# 2021-03-01_HALO_Main_Board.net
KiCad netlist of a schematic drawn in EAGLE
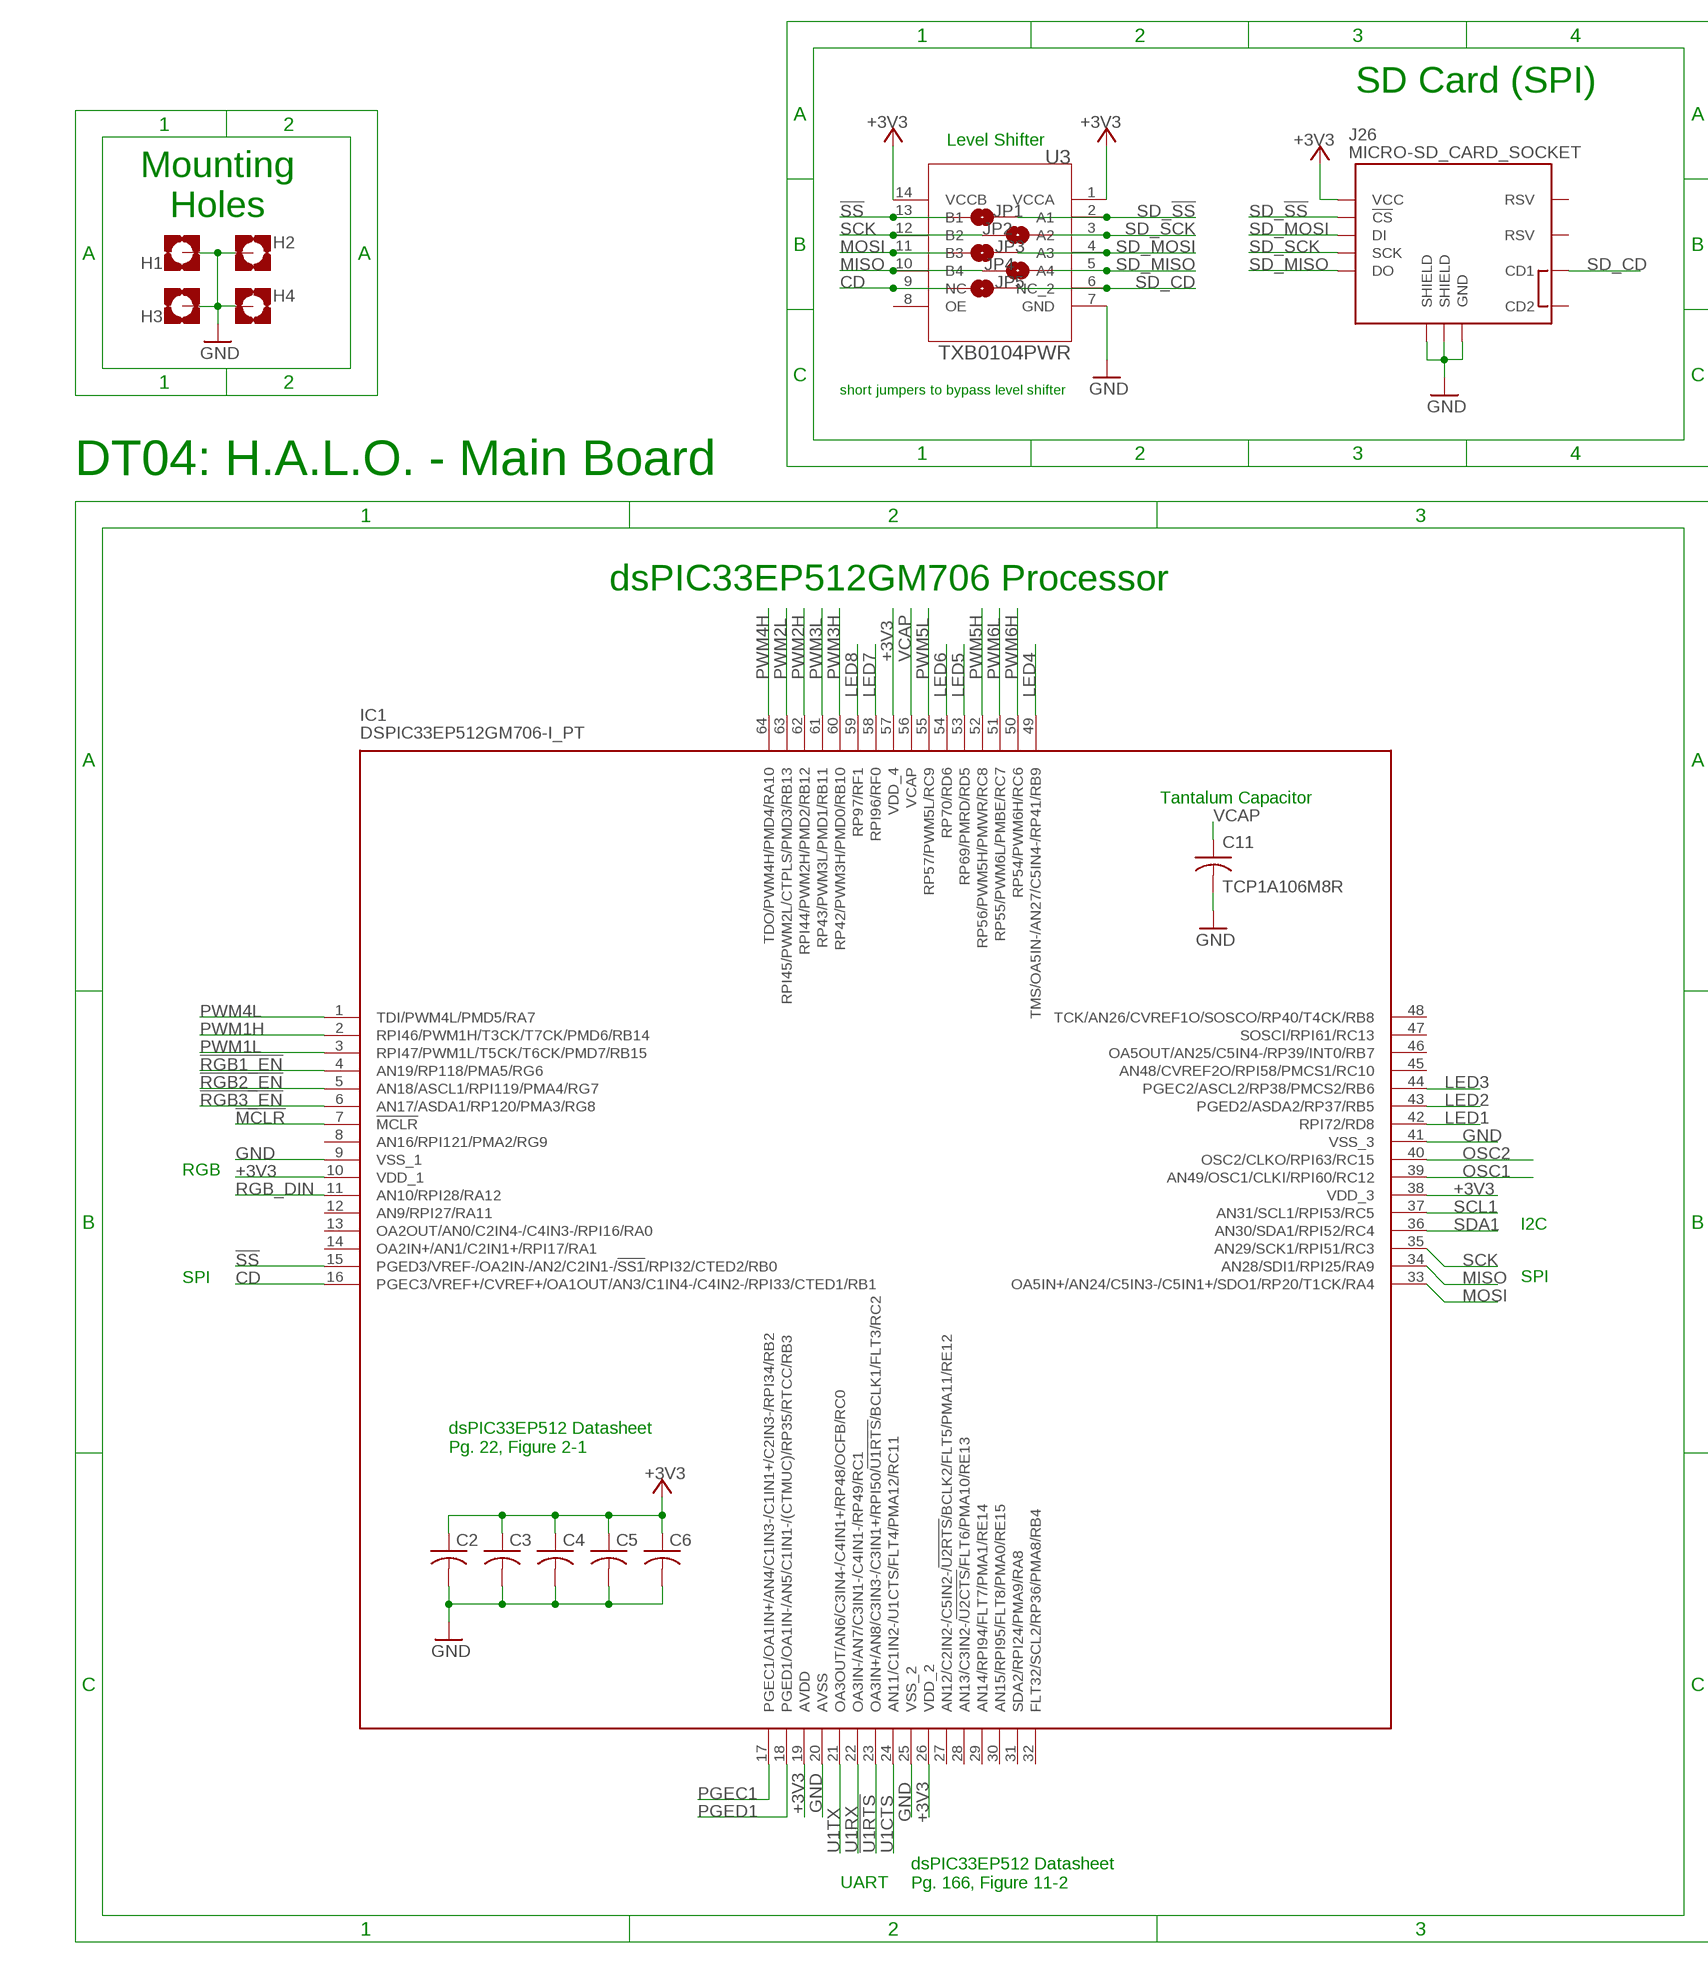
[diagram p0: schematic, sheet 1, part 1 of 2]
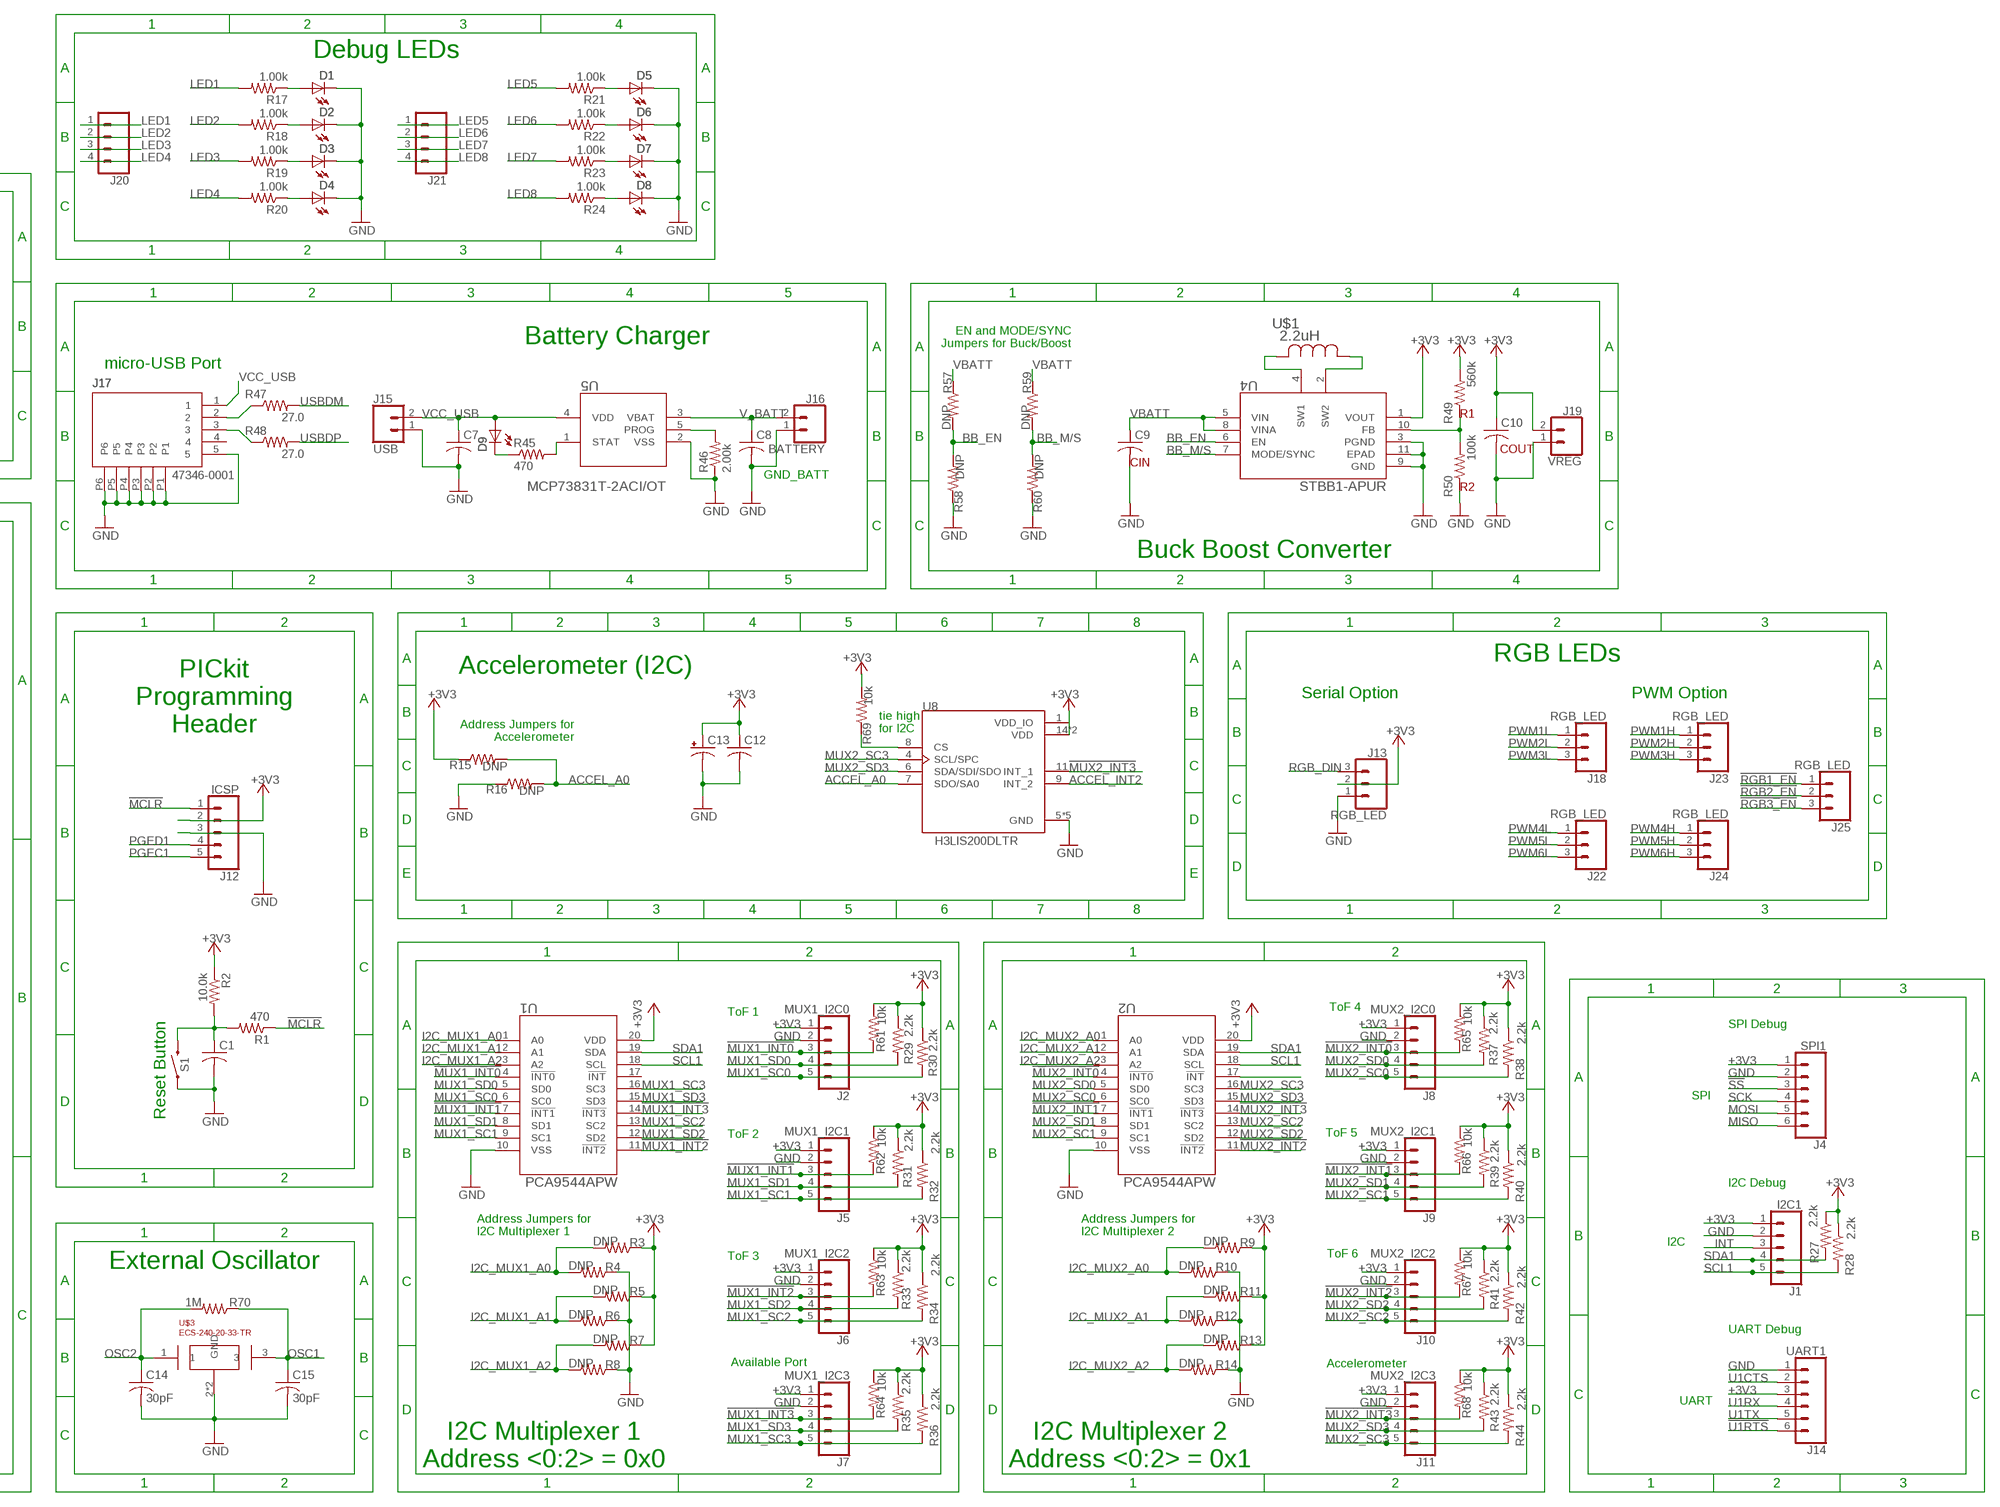
[diagram p1: schematic, sheet 1, part 2 of 2]

(export (version "E")
  (design (tool "Eeschema 10.0.6"))
  (components
    (comp (ref "C1")
      (value "0.1uF")
      (footprint "eagle-import:C0805")
      (libsource (lib "eagle-import") (part "rcl_C-USC0805"))
    )
    (comp (ref "C2")
      (value "0.1uF")
      (footprint "eagle-import:C0805")
      (libsource (lib "eagle-import") (part "rcl_C-USC0805"))
    )
    (comp (ref "C3")
      (value "0.1uF")
      (footprint "eagle-import:C0805")
      (libsource (lib "eagle-import") (part "rcl_C-USC0805"))
    )
    (comp (ref "C4")
      (value "0.1uF")
      (footprint "eagle-import:C0805")
      (libsource (lib "eagle-import") (part "rcl_C-USC0805"))
    )
    (comp (ref "C5")
      (value "0.1uF")
      (footprint "eagle-import:C0805")
      (libsource (lib "eagle-import") (part "rcl_C-USC0805"))
    )
    (comp (ref "C6")
      (value "0.1uF")
      (footprint "eagle-import:C0805")
      (libsource (lib "eagle-import") (part "rcl_C-USC0805"))
    )
    (comp (ref "C7")
      (value "4.7uF")
      (footprint "eagle-import:C0805")
      (libsource (lib "eagle-import") (part "rcl_C-USC0805"))
    )
    (comp (ref "C8")
      (value "4.7uF")
      (footprint "eagle-import:C0805")
      (libsource (lib "eagle-import") (part "rcl_C-USC0805"))
    )
    (comp (ref "C9")
      (value "10uF")
      (footprint "eagle-import:C0805")
      (libsource (lib "eagle-import") (part "rcl_C-USC0805"))
    )
    (comp (ref "C10")
      (value "22uF")
      (footprint "eagle-import:C0805")
      (libsource (lib "eagle-import") (part "rcl_C-USC0805"))
    )
    (comp (ref "C11")
      (value "TCP1A106M8R")
      (footprint "eagle-import:TCP_ROM")
      (libsource (lib "eagle-import") (part "TCP1A106M8R"))
    )
    (comp (ref "C12")
      (value "0.1uF")
      (footprint "eagle-import:C0805")
      (libsource (lib "eagle-import") (part "rcl_C-USC0805"))
    )
    (comp (ref "C13")
      (value "10uF")
      (footprint "eagle-import:EIA3216")
      (libsource (lib "eagle-import") (part "10UF-POLAR-EIA3216-16V-10%(TANT)"))
    )
    (comp (ref "C14")
      (value "30pF")
      (footprint "eagle-import:C0805")
      (libsource (lib "eagle-import") (part "C-USC0805"))
    )
    (comp (ref "C15")
      (value "30pF")
      (footprint "eagle-import:C0805")
      (libsource (lib "eagle-import") (part "C-USC0805"))
    )
    (comp (ref "D1")
      (value "CHIP-LED0805")
      (footprint "eagle-import:CHIP-LED0805")
      (libsource (lib "eagle-import") (part "CHIP-LED0805"))
    )
    (comp (ref "D2")
      (value "CHIP-LED0805")
      (footprint "eagle-import:CHIP-LED0805")
      (libsource (lib "eagle-import") (part "CHIP-LED0805"))
    )
    (comp (ref "D3")
      (value "CHIP-LED0805")
      (footprint "eagle-import:CHIP-LED0805")
      (libsource (lib "eagle-import") (part "CHIP-LED0805"))
    )
    (comp (ref "D4")
      (value "CHIP-LED0805")
      (footprint "eagle-import:CHIP-LED0805")
      (libsource (lib "eagle-import") (part "CHIP-LED0805"))
    )
    (comp (ref "D5")
      (value "CHIP-LED0805")
      (footprint "eagle-import:CHIP-LED0805")
      (libsource (lib "eagle-import") (part "CHIP-LED0805"))
    )
    (comp (ref "D6")
      (value "CHIP-LED0805")
      (footprint "eagle-import:CHIP-LED0805")
      (libsource (lib "eagle-import") (part "CHIP-LED0805"))
    )
    (comp (ref "D7")
      (value "CHIP-LED0805")
      (footprint "eagle-import:CHIP-LED0805")
      (libsource (lib "eagle-import") (part "CHIP-LED0805"))
    )
    (comp (ref "D8")
      (value "CHIP-LED0805")
      (footprint "eagle-import:CHIP-LED0805")
      (libsource (lib "eagle-import") (part "CHIP-LED0805"))
    )
    (comp (ref "D9")
      (value "CHIP-LED0805")
      (footprint "eagle-import:CHIP-LED0805")
      (libsource (lib "eagle-import") (part "CHIP-LED0805"))
    )
    (comp (ref "H1")
      (value "MOUNT-PAD-SQUARE3.0")
      (footprint "eagle-import:3,0-PAD-SQUARE")
      (libsource (lib "eagle-import") (part "MOUNT-PAD-SQUARE3.0"))
    )
    (comp (ref "H2")
      (value "MOUNT-PAD-SQUARE3.0")
      (footprint "eagle-import:3,0-PAD-SQUARE")
      (libsource (lib "eagle-import") (part "MOUNT-PAD-SQUARE3.0"))
    )
    (comp (ref "H3")
      (value "MOUNT-PAD-SQUARE3.0")
      (footprint "eagle-import:3,0-PAD-SQUARE")
      (libsource (lib "eagle-import") (part "MOUNT-PAD-SQUARE3.0"))
    )
    (comp (ref "H4")
      (value "MOUNT-PAD-SQUARE3.0")
      (footprint "eagle-import:3,0-PAD-SQUARE")
      (libsource (lib "eagle-import") (part "MOUNT-PAD-SQUARE3.0"))
    )
    (comp (ref "IC1")
      (value "DSPIC33EP512GM706-I_PT")
      (footprint "eagle-import:QFP50P1200X1200X120-64N")
      (fields
        (field (name "ARROW_PART_NUMBER") "DSPIC33EP512GM706-I/PT")
        (field (name "MOUSER_PART_NUMBER") "579-512GM706-I/PT")
      )
      (libsource (lib "eagle-import") (part "DSPIC33EP512GM706-I_PT"))
    )
    (comp (ref "J1")
      (value "I2C1")
      (footprint "eagle-import:1X05")
      (libsource (lib "eagle-import") (part "CONN_05"))
    )
    (comp (ref "J2")
      (value "MUX1_I2C0")
      (footprint "eagle-import:1X05")
      (libsource (lib "eagle-import") (part "CONN_05"))
    )
    (comp (ref "J4")
      (value "SPI1")
      (footprint "eagle-import:1X06")
      (libsource (lib "eagle-import") (part "CONN_06SILK_FEMALE_PTH"))
    )
    (comp (ref "J5")
      (value "MUX1_I2C1")
      (footprint "eagle-import:1X05")
      (libsource (lib "eagle-import") (part "CONN_05"))
    )
    (comp (ref "J6")
      (value "MUX1_I2C2")
      (footprint "eagle-import:1X05")
      (libsource (lib "eagle-import") (part "CONN_05"))
    )
    (comp (ref "J7")
      (value "MUX1_I2C3")
      (footprint "eagle-import:1X05")
      (libsource (lib "eagle-import") (part "CONN_05"))
    )
    (comp (ref "J8")
      (value "MUX2_I2C0")
      (footprint "eagle-import:1X05")
      (libsource (lib "eagle-import") (part "CONN_05"))
    )
    (comp (ref "J9")
      (value "MUX2_I2C1")
      (footprint "eagle-import:1X05")
      (libsource (lib "eagle-import") (part "CONN_05"))
    )
    (comp (ref "J10")
      (value "MUX2_I2C2")
      (footprint "eagle-import:1X05")
      (libsource (lib "eagle-import") (part "CONN_05"))
    )
    (comp (ref "J11")
      (value "MUX2_I2C3")
      (footprint "eagle-import:1X05")
      (libsource (lib "eagle-import") (part "CONN_05"))
    )
    (comp (ref "J12")
      (value "ICSP")
      (footprint "eagle-import:1X05")
      (libsource (lib "eagle-import") (part "CONN_05"))
    )
    (comp (ref "J13")
      (value "RGB_LED")
      (footprint "eagle-import:1X03_LOCK")
      (libsource (lib "eagle-import") (part "CONN_03LOCK"))
    )
    (comp (ref "J14")
      (value "UART1")
      (footprint "eagle-import:1X06")
      (libsource (lib "eagle-import") (part "CONN_06SILK_FEMALE_PTH"))
    )
    (comp (ref "J15")
      (value "USB")
      (footprint "eagle-import:1X02")
      (libsource (lib "eagle-import") (part "CONN_02"))
    )
    (comp (ref "J16")
      (value "BATTERY")
      (footprint "eagle-import:1X02")
      (libsource (lib "eagle-import") (part "CONN_02"))
    )
    (comp (ref "J17")
      (value "47346-0001")
      (footprint "eagle-import:MICRO_USB")
      (fields (field (name "PARTNO") "AS-ITM-00021") (field (name "PARTNO_1") "AS-ITM-00021"))
      (libsource (lib "eagle-import") (part "AS-ITM-00021"))
    )
    (comp (ref "J18")
      (value "RGB_LED")
      (footprint "eagle-import:1X03_LOCK")
      (libsource (lib "eagle-import") (part "CONN_03LOCK"))
    )
    (comp (ref "J19")
      (value "VREG")
      (footprint "eagle-import:1X02")
      (libsource (lib "eagle-import") (part "CONN_02"))
    )
    (comp (ref "J20")
      (value "CONN_04")
      (footprint "eagle-import:1X04")
      (libsource (lib "eagle-import") (part "CONN_04"))
    )
    (comp (ref "J21")
      (value "CONN_04")
      (footprint "eagle-import:1X04")
      (libsource (lib "eagle-import") (part "CONN_04"))
    )
    (comp (ref "J22")
      (value "RGB_LED")
      (footprint "eagle-import:1X03_LOCK")
      (libsource (lib "eagle-import") (part "CONN_03LOCK"))
    )
    (comp (ref "J23")
      (value "RGB_LED")
      (footprint "eagle-import:1X03_LOCK")
      (libsource (lib "eagle-import") (part "CONN_03LOCK"))
    )
    (comp (ref "J24")
      (value "RGB_LED")
      (footprint "eagle-import:1X03_LOCK")
      (libsource (lib "eagle-import") (part "CONN_03LOCK"))
    )
    (comp (ref "J25")
      (value "RGB_LED")
      (footprint "eagle-import:1X03_LOCK")
      (libsource (lib "eagle-import") (part "CONN_03LOCK"))
    )
    (comp (ref "J26")
      (value "MICRO-SD_CARD_SOCKET")
      (footprint "eagle-import:MICRO-SD-SOCKET")
      (libsource (lib "eagle-import") (part "MICRO-SD_CARD_SOCKET"))
    )
    (comp (ref "JP1")
      (value "JUMPER-SMT_2_NO_NO-SILK")
      (footprint "eagle-import:SMT-JUMPER_2_NO_NO-SILK")
      (libsource (lib "eagle-import") (part "JUMPER-SMT_2_NO_NO-SILK"))
    )
    (comp (ref "JP2")
      (value "JUMPER-SMT_2_NO_NO-SILK")
      (footprint "eagle-import:SMT-JUMPER_2_NO_NO-SILK")
      (libsource (lib "eagle-import") (part "JUMPER-SMT_2_NO_NO-SILK"))
    )
    (comp (ref "JP3")
      (value "JUMPER-SMT_2_NO_NO-SILK")
      (footprint "eagle-import:SMT-JUMPER_2_NO_NO-SILK")
      (libsource (lib "eagle-import") (part "JUMPER-SMT_2_NO_NO-SILK"))
    )
    (comp (ref "JP4")
      (value "JUMPER-SMT_2_NO_NO-SILK")
      (footprint "eagle-import:SMT-JUMPER_2_NO_NO-SILK")
      (libsource (lib "eagle-import") (part "JUMPER-SMT_2_NO_NO-SILK"))
    )
    (comp (ref "JP5")
      (value "JUMPER-SMT_2_NO_NO-SILK")
      (footprint "eagle-import:SMT-JUMPER_2_NO_NO-SILK")
      (libsource (lib "eagle-import") (part "JUMPER-SMT_2_NO_NO-SILK"))
    )
    (comp (ref "R1")
      (value "470")
      (footprint "eagle-import:R0805")
      (libsource (lib "eagle-import") (part "R-US_R0805"))
    )
    (comp (ref "R2")
      (value "10.0k")
      (footprint "eagle-import:R0805")
      (libsource (lib "eagle-import") (part "R-US_R0805"))
    )
    (comp (ref "R3")
      (value "DNP")
      (footprint "eagle-import:R0805")
      (libsource (lib "eagle-import") (part "R-US_R0805"))
    )
    (comp (ref "R4")
      (value "DNP")
      (footprint "eagle-import:R0805")
      (libsource (lib "eagle-import") (part "R-US_R0805"))
    )
    (comp (ref "R5")
      (value "DNP")
      (footprint "eagle-import:R0805")
      (libsource (lib "eagle-import") (part "R-US_R0805"))
    )
    (comp (ref "R6")
      (value "DNP")
      (footprint "eagle-import:R0805")
      (libsource (lib "eagle-import") (part "R-US_R0805"))
    )
    (comp (ref "R7")
      (value "DNP")
      (footprint "eagle-import:R0805")
      (libsource (lib "eagle-import") (part "R-US_R0805"))
    )
    (comp (ref "R8")
      (value "DNP")
      (footprint "eagle-import:R0805")
      (libsource (lib "eagle-import") (part "R-US_R0805"))
    )
    (comp (ref "R9")
      (value "DNP")
      (footprint "eagle-import:R0805")
      (libsource (lib "eagle-import") (part "R-US_R0805"))
    )
    (comp (ref "R10")
      (value "DNP")
      (footprint "eagle-import:R0805")
      (libsource (lib "eagle-import") (part "R-US_R0805"))
    )
    (comp (ref "R11")
      (value "DNP")
      (footprint "eagle-import:R0805")
      (libsource (lib "eagle-import") (part "R-US_R0805"))
    )
    (comp (ref "R12")
      (value "DNP")
      (footprint "eagle-import:R0805")
      (libsource (lib "eagle-import") (part "R-US_R0805"))
    )
    (comp (ref "R13")
      (value "DNP")
      (footprint "eagle-import:R0805")
      (libsource (lib "eagle-import") (part "R-US_R0805"))
    )
    (comp (ref "R14")
      (value "DNP")
      (footprint "eagle-import:R0805")
      (libsource (lib "eagle-import") (part "R-US_R0805"))
    )
    (comp (ref "R15")
      (value "DNP")
      (footprint "eagle-import:R0805")
      (libsource (lib "eagle-import") (part "R-US_R0805"))
    )
    (comp (ref "R16")
      (value "DNP")
      (footprint "eagle-import:R0805")
      (libsource (lib "eagle-import") (part "R-US_R0805"))
    )
    (comp (ref "R17")
      (value "1.00k")
      (footprint "eagle-import:R0805")
      (libsource (lib "eagle-import") (part "R-US_R0805"))
    )
    (comp (ref "R18")
      (value "1.00k")
      (footprint "eagle-import:R0805")
      (libsource (lib "eagle-import") (part "R-US_R0805"))
    )
    (comp (ref "R19")
      (value "1.00k")
      (footprint "eagle-import:R0805")
      (libsource (lib "eagle-import") (part "R-US_R0805"))
    )
    (comp (ref "R20")
      (value "1.00k")
      (footprint "eagle-import:R0805")
      (libsource (lib "eagle-import") (part "R-US_R0805"))
    )
    (comp (ref "R21")
      (value "1.00k")
      (footprint "eagle-import:R0805")
      (libsource (lib "eagle-import") (part "R-US_R0805"))
    )
    (comp (ref "R22")
      (value "1.00k")
      (footprint "eagle-import:R0805")
      (libsource (lib "eagle-import") (part "R-US_R0805"))
    )
    (comp (ref "R23")
      (value "1.00k")
      (footprint "eagle-import:R0805")
      (libsource (lib "eagle-import") (part "R-US_R0805"))
    )
    (comp (ref "R24")
      (value "1.00k")
      (footprint "eagle-import:R0805")
      (libsource (lib "eagle-import") (part "R-US_R0805"))
    )
    (comp (ref "R27")
      (value "2.2k")
      (footprint "eagle-import:R0805")
      (libsource (lib "eagle-import") (part "R-US_R0805"))
    )
    (comp (ref "R28")
      (value "2.2k")
      (footprint "eagle-import:R0805")
      (libsource (lib "eagle-import") (part "R-US_R0805"))
    )
    (comp (ref "R29")
      (value "2.2k")
      (footprint "eagle-import:R0805")
      (libsource (lib "eagle-import") (part "R-US_R0805"))
    )
    (comp (ref "R30")
      (value "2.2k")
      (footprint "eagle-import:R0805")
      (libsource (lib "eagle-import") (part "R-US_R0805"))
    )
    (comp (ref "R31")
      (value "2.2k")
      (footprint "eagle-import:R0805")
      (libsource (lib "eagle-import") (part "R-US_R0805"))
    )
    (comp (ref "R32")
      (value "2.2k")
      (footprint "eagle-import:R0805")
      (libsource (lib "eagle-import") (part "R-US_R0805"))
    )
    (comp (ref "R33")
      (value "2.2k")
      (footprint "eagle-import:R0805")
      (libsource (lib "eagle-import") (part "R-US_R0805"))
    )
    (comp (ref "R34")
      (value "2.2k")
      (footprint "eagle-import:R0805")
      (libsource (lib "eagle-import") (part "R-US_R0805"))
    )
    (comp (ref "R35")
      (value "2.2k")
      (footprint "eagle-import:R0805")
      (libsource (lib "eagle-import") (part "R-US_R0805"))
    )
    (comp (ref "R36")
      (value "2.2k")
      (footprint "eagle-import:R0805")
      (libsource (lib "eagle-import") (part "R-US_R0805"))
    )
    (comp (ref "R37")
      (value "2.2k")
      (footprint "eagle-import:R0805")
      (libsource (lib "eagle-import") (part "R-US_R0805"))
    )
    (comp (ref "R38")
      (value "2.2k")
      (footprint "eagle-import:R0805")
      (libsource (lib "eagle-import") (part "R-US_R0805"))
    )
    (comp (ref "R39")
      (value "2.2k")
      (footprint "eagle-import:R0805")
      (libsource (lib "eagle-import") (part "R-US_R0805"))
    )
    (comp (ref "R40")
      (value "2.2k")
      (footprint "eagle-import:R0805")
      (libsource (lib "eagle-import") (part "R-US_R0805"))
    )
    (comp (ref "R41")
      (value "2.2k")
      (footprint "eagle-import:R0805")
      (libsource (lib "eagle-import") (part "R-US_R0805"))
    )
    (comp (ref "R42")
      (value "2.2k")
      (footprint "eagle-import:R0805")
      (libsource (lib "eagle-import") (part "R-US_R0805"))
    )
    (comp (ref "R43")
      (value "2.2k")
      (footprint "eagle-import:R0805")
      (libsource (lib "eagle-import") (part "R-US_R0805"))
    )
    (comp (ref "R44")
      (value "2.2k")
      (footprint "eagle-import:R0805")
      (libsource (lib "eagle-import") (part "R-US_R0805"))
    )
    (comp (ref "R45")
      (value "470")
      (footprint "eagle-import:R0805")
      (libsource (lib "eagle-import") (part "R-US_R0805"))
    )
    (comp (ref "R46")
      (value "2.00k")
      (footprint "eagle-import:R0805")
      (libsource (lib "eagle-import") (part "R-US_R0805"))
    )
    (comp (ref "R47")
      (value "27.0")
      (footprint "eagle-import:R0805")
      (libsource (lib "eagle-import") (part "R-US_R0805"))
    )
    (comp (ref "R48")
      (value "27.0")
      (footprint "eagle-import:R0805")
      (libsource (lib "eagle-import") (part "R-US_R0805"))
    )
    (comp (ref "R49")
      (value "560k")
      (footprint "eagle-import:R0805")
      (libsource (lib "eagle-import") (part "R-US_R0805"))
    )
    (comp (ref "R50")
      (value "100k")
      (footprint "eagle-import:R0805")
      (libsource (lib "eagle-import") (part "R-US_R0805"))
    )
    (comp (ref "R57")
      (value "DNP")
      (footprint "eagle-import:R0805")
      (libsource (lib "eagle-import") (part "R-US_R0805"))
    )
    (comp (ref "R58")
      (value "DNP")
      (footprint "eagle-import:R0805")
      (libsource (lib "eagle-import") (part "R-US_R0805"))
    )
    (comp (ref "R59")
      (value "DNP")
      (footprint "eagle-import:R0805")
      (libsource (lib "eagle-import") (part "R-US_R0805"))
    )
    (comp (ref "R60")
      (value "DNP")
      (footprint "eagle-import:R0805")
      (libsource (lib "eagle-import") (part "R-US_R0805"))
    )
    (comp (ref "R61")
      (value "10k")
      (footprint "eagle-import:R0805")
      (libsource (lib "eagle-import") (part "R-US_R0805"))
    )
    (comp (ref "R62")
      (value "10k")
      (footprint "eagle-import:R0805")
      (libsource (lib "eagle-import") (part "R-US_R0805"))
    )
    (comp (ref "R63")
      (value "10k")
      (footprint "eagle-import:R0805")
      (libsource (lib "eagle-import") (part "R-US_R0805"))
    )
    (comp (ref "R64")
      (value "10k")
      (footprint "eagle-import:R0805")
      (libsource (lib "eagle-import") (part "R-US_R0805"))
    )
    (comp (ref "R65")
      (value "10k")
      (footprint "eagle-import:R0805")
      (libsource (lib "eagle-import") (part "R-US_R0805"))
    )
    (comp (ref "R66")
      (value "10k")
      (footprint "eagle-import:R0805")
      (libsource (lib "eagle-import") (part "R-US_R0805"))
    )
    (comp (ref "R67")
      (value "10k")
      (footprint "eagle-import:R0805")
      (libsource (lib "eagle-import") (part "R-US_R0805"))
    )
    (comp (ref "R68")
      (value "10k")
      (footprint "eagle-import:R0805")
      (libsource (lib "eagle-import") (part "R-US_R0805"))
    )
    (comp (ref "R69")
      (value "10k")
      (footprint "eagle-import:R0805")
      (libsource (lib "eagle-import") (part "R-US_R0805"))
    )
    (comp (ref "R70")
      (value "1M")
      (footprint "eagle-import:R0805")
      (libsource (lib "eagle-import") (part "R-US_R0805"))
    )
    (comp (ref "S1")
      (value "SWITCH-MOMENTARY-2SMD-4")
      (footprint "eagle-import:TACTILE_SWITCH_TALL")
      (libsource (lib "eagle-import") (part "SWITCH-MOMENTARY-2SMD-4"))
    )
    (comp (ref "U$1")
      (value "2.2uH")
      (footprint "eagle-import:IND_4028_TDK")
      (libsource (lib "eagle-import") (part "IND"))
    )
    (comp (ref "U$3")
      (value "ECS-240-20-33-TR")
      (footprint "eagle-import:ECX-32")
      (libsource (lib "eagle-import") (part "ECS-240-20-33-TR"))
    )
    (comp (ref "U1")
      (value "PCA9544APW")
      (footprint "eagle-import:SOT360-1_NXP")
      (libsource (lib "eagle-import") (part "PCA9544APW"))
    )
    (comp (ref "U2")
      (value "PCA9544APW")
      (footprint "eagle-import:SOT360-1_NXP")
      (libsource (lib "eagle-import") (part "PCA9544APW"))
    )
    (comp (ref "U3")
      (value "TXB0104PWR")
      (footprint "eagle-import:PW14")
      (fields
        (field (name "GENERIC_PART_NUMBER") "TXB0104")
        (field (name "MANUFACTURER") "Texas Instruments")
      )
      (libsource (lib "eagle-import") (part "TXB0104PWR"))
    )
    (comp (ref "U4")
      (value "STBB1-APUR")
      (footprint "eagle-import:SON_B1-APUR_STM")
      (libsource (lib "eagle-import") (part "STBB1-APUR"))
    )
    (comp (ref "U5")
      (value "MCP73831T-2ACI/OT")
      (footprint "eagle-import:SOT-23-5_MC_MCH")
      (libsource (lib "eagle-import") (part "MCP73831T-2ACI/OT"))
    )
    (comp (ref "U8")
      (value "H3LIS200DLTR")
      (footprint "eagle-import:PQFN50P300X300X100-16N")
      (fields (field (name "DIGI-KEY_PART_NUMBER") "497-15698-1-ND") (field (name "MF") "STMicroelectronics"))
      (libsource (lib "eagle-import") (part "H3LIS200DLTR"))
    )
  )
  (nets
    (net (code "1") (name "+3V3") (class "Default")
      (node (ref "C10") (pin "1") (pinfunction "1_1") (pintype "passive"))
      (node (ref "C12") (pin "1") (pinfunction "1_1") (pintype "passive"))
      (node (ref "C13") (pin "+") (pinfunction "+_+") (pintype "passive"))
      (node (ref "C2") (pin "1") (pinfunction "1_1") (pintype "passive"))
      (node (ref "C3") (pin "1") (pinfunction "1_1") (pintype "passive"))
      (node (ref "C4") (pin "1") (pinfunction "1_1") (pintype "passive"))
      (node (ref "C5") (pin "1") (pinfunction "1_1") (pintype "passive"))
      (node (ref "C6") (pin "1") (pinfunction "1_1") (pintype "passive"))
      (node (ref "IC1") (pin "10") (pinfunction "VDD_1_10") (pintype "bidirectional"))
      (node (ref "IC1") (pin "19") (pinfunction "AVDD_19") (pintype "bidirectional"))
      (node (ref "IC1") (pin "26") (pinfunction "VDD_2_26") (pintype "bidirectional"))
      (node (ref "IC1") (pin "38") (pinfunction "VDD_3_38") (pintype "bidirectional"))
      (node (ref "IC1") (pin "57") (pinfunction "VDD_4_57") (pintype "bidirectional"))
      (node (ref "J1") (pin "1") (pinfunction "1_1") (pintype "passive"))
      (node (ref "J10") (pin "1") (pinfunction "1_1") (pintype "passive"))
      (node (ref "J11") (pin "1") (pinfunction "1_1") (pintype "passive"))
      (node (ref "J12") (pin "2") (pinfunction "2_2") (pintype "passive"))
      (node (ref "J13") (pin "2") (pinfunction "2_2") (pintype "passive"))
      (node (ref "J14") (pin "3") (pinfunction "3_3") (pintype "passive"))
      (node (ref "J19") (pin "2") (pinfunction "2_2") (pintype "passive"))
      (node (ref "J2") (pin "1") (pinfunction "1_1") (pintype "passive"))
      (node (ref "J26") (pin "VCC") (pinfunction "VCC_VCC") (pintype "bidirectional"))
      (node (ref "J4") (pin "1") (pinfunction "1_1") (pintype "passive"))
      (node (ref "J5") (pin "1") (pinfunction "1_1") (pintype "passive"))
      (node (ref "J6") (pin "1") (pinfunction "1_1") (pintype "passive"))
      (node (ref "J7") (pin "1") (pinfunction "1_1") (pintype "passive"))
      (node (ref "J8") (pin "1") (pinfunction "1_1") (pintype "passive"))
      (node (ref "J9") (pin "1") (pinfunction "1_1") (pintype "passive"))
      (node (ref "R11") (pin "1") (pinfunction "1_1") (pintype "passive"))
      (node (ref "R13") (pin "1") (pinfunction "1_1") (pintype "passive"))
      (node (ref "R15") (pin "1") (pinfunction "1_1") (pintype "passive"))
      (node (ref "R2") (pin "1") (pinfunction "1_1") (pintype "passive"))
      (node (ref "R27") (pin "1") (pinfunction "1_1") (pintype "passive"))
      (node (ref "R28") (pin "1") (pinfunction "1_1") (pintype "passive"))
      (node (ref "R29") (pin "1") (pinfunction "1_1") (pintype "passive"))
      (node (ref "R3") (pin "1") (pinfunction "1_1") (pintype "passive"))
      (node (ref "R30") (pin "1") (pinfunction "1_1") (pintype "passive"))
      (node (ref "R31") (pin "1") (pinfunction "1_1") (pintype "passive"))
      (node (ref "R32") (pin "1") (pinfunction "1_1") (pintype "passive"))
      (node (ref "R33") (pin "1") (pinfunction "1_1") (pintype "passive"))
      (node (ref "R34") (pin "1") (pinfunction "1_1") (pintype "passive"))
      (node (ref "R35") (pin "1") (pinfunction "1_1") (pintype "passive"))
      (node (ref "R36") (pin "1") (pinfunction "1_1") (pintype "passive"))
      (node (ref "R37") (pin "1") (pinfunction "1_1") (pintype "passive"))
      (node (ref "R38") (pin "1") (pinfunction "1_1") (pintype "passive"))
      (node (ref "R39") (pin "1") (pinfunction "1_1") (pintype "passive"))
      (node (ref "R40") (pin "1") (pinfunction "1_1") (pintype "passive"))
      (node (ref "R41") (pin "1") (pinfunction "1_1") (pintype "passive"))
      (node (ref "R42") (pin "1") (pinfunction "1_1") (pintype "passive"))
      (node (ref "R43") (pin "1") (pinfunction "1_1") (pintype "passive"))
      (node (ref "R44") (pin "1") (pinfunction "1_1") (pintype "passive"))
      (node (ref "R49") (pin "2") (pinfunction "2_2") (pintype "passive"))
      (node (ref "R5") (pin "1") (pinfunction "1_1") (pintype "passive"))
      (node (ref "R61") (pin "1") (pinfunction "1_1") (pintype "passive"))
      (node (ref "R62") (pin "1") (pinfunction "1_1") (pintype "passive"))
      (node (ref "R63") (pin "1") (pinfunction "1_1") (pintype "passive"))
      (node (ref "R64") (pin "1") (pinfunction "1_1") (pintype "passive"))
      (node (ref "R65") (pin "1") (pinfunction "1_1") (pintype "passive"))
      (node (ref "R66") (pin "1") (pinfunction "1_1") (pintype "passive"))
      (node (ref "R67") (pin "1") (pinfunction "1_1") (pintype "passive"))
      (node (ref "R68") (pin "1") (pinfunction "1_1") (pintype "passive"))
      (node (ref "R69") (pin "2") (pinfunction "2_2") (pintype "passive"))
      (node (ref "R7") (pin "1") (pinfunction "1_1") (pintype "passive"))
      (node (ref "R9") (pin "1") (pinfunction "1_1") (pintype "passive"))
      (node (ref "U1") (pin "20") (pinfunction "VDD_20") (pintype "passive"))
      (node (ref "U2") (pin "20") (pinfunction "VDD_20") (pintype "passive"))
      (node (ref "U3") (pin "1") (pinfunction "VCCA_1") (pintype "power_in"))
      (node (ref "U3") (pin "14") (pinfunction "VCCB_14") (pintype "power_in"))
      (node (ref "U4") (pin "1") (pinfunction "VOUT_1") (pintype "power_in"))
      (node (ref "U8") (pin "1") (pinfunction "VDD_IO_1") (pintype "power_in"))
      (node (ref "U8") (pin "14") (pinfunction "VDD_14") (pintype "power_in"))
      (node (ref "U8") (pin "15") (pinfunction "VDD_15") (pintype "power_in"))
    )
    (net (code "2") (name "/ACCEL_A0") (class "Default")
      (node (ref "R15") (pin "2") (pinfunction "2_2") (pintype "passive"))
      (node (ref "R16") (pin "2") (pinfunction "2_2") (pintype "passive"))
      (node (ref "U8") (pin "7") (pinfunction "SDO/SA0_7") (pintype "output"))
    )
    (net (code "3") (name "/ACCEL_INT2") (class "Default")
      (node (ref "U8") (pin "9") (pinfunction "INT_2_9") (pintype "output"))
    )
    (net (code "4") (name "/BB_EN") (class "Default")
      (node (ref "R57") (pin "2") (pinfunction "2_2") (pintype "passive"))
      (node (ref "R58") (pin "2") (pinfunction "2_2") (pintype "passive"))
      (node (ref "U4") (pin "6") (pinfunction "EN_6") (pintype "passive"))
    )
    (net (code "5") (name "/BB_M{slash}S") (class "Default")
      (node (ref "R59") (pin "2") (pinfunction "2_2") (pintype "passive"))
      (node (ref "R60") (pin "2") (pinfunction "2_2") (pintype "passive"))
      (node (ref "U4") (pin "7") (pinfunction "MODE/SYNC_7") (pintype "passive"))
    )
    (net (code "6") (name "/CD") (class "Default")
      (node (ref "IC1") (pin "16") (pinfunction "PGEC3/VREF+/CVREF+/OA1OUT/AN3/C1IN4-/C4IN2-/RPI33/CTED1/RB1_16") (pintype "bidirectional"))
      (node (ref "JP5") (pin "2") (pinfunction "2_2") (pintype "passive"))
      (node (ref "U3") (pin "9") (pinfunction "NC_9") (pintype "passive"))
    )
    (net (code "7") (name "/I2C_MUX1_A0") (class "Default")
      (node (ref "R3") (pin "2") (pinfunction "2_2") (pintype "passive"))
      (node (ref "R4") (pin "2") (pinfunction "2_2") (pintype "passive"))
      (node (ref "U1") (pin "1") (pinfunction "A0_1") (pintype "passive"))
    )
    (net (code "8") (name "/I2C_MUX1_A1") (class "Default")
      (node (ref "R5") (pin "2") (pinfunction "2_2") (pintype "passive"))
      (node (ref "R6") (pin "2") (pinfunction "2_2") (pintype "passive"))
      (node (ref "U1") (pin "2") (pinfunction "A1_2") (pintype "passive"))
    )
    (net (code "9") (name "/I2C_MUX1_A2") (class "Default")
      (node (ref "R7") (pin "2") (pinfunction "2_2") (pintype "passive"))
      (node (ref "R8") (pin "2") (pinfunction "2_2") (pintype "passive"))
      (node (ref "U1") (pin "3") (pinfunction "A2_3") (pintype "passive"))
    )
    (net (code "10") (name "/I2C_MUX2_A0") (class "Default")
      (node (ref "R10") (pin "2") (pinfunction "2_2") (pintype "passive"))
      (node (ref "R9") (pin "2") (pinfunction "2_2") (pintype "passive"))
      (node (ref "U2") (pin "1") (pinfunction "A0_1") (pintype "passive"))
    )
    (net (code "11") (name "/I2C_MUX2_A1") (class "Default")
      (node (ref "R11") (pin "2") (pinfunction "2_2") (pintype "passive"))
      (node (ref "R12") (pin "2") (pinfunction "2_2") (pintype "passive"))
      (node (ref "U2") (pin "2") (pinfunction "A1_2") (pintype "passive"))
    )
    (net (code "12") (name "/I2C_MUX2_A2") (class "Default")
      (node (ref "R13") (pin "2") (pinfunction "2_2") (pintype "passive"))
      (node (ref "R14") (pin "2") (pinfunction "2_2") (pintype "passive"))
      (node (ref "U2") (pin "3") (pinfunction "A2_3") (pintype "passive"))
    )
    (net (code "13") (name "/INT") (class "Default")
      (node (ref "J1") (pin "3") (pinfunction "3_3") (pintype "passive"))
    )
    (net (code "14") (name "/LED1") (class "Default")
      (node (ref "IC1") (pin "42") (pinfunction "RPI72/RD8_42") (pintype "bidirectional"))
      (node (ref "J20") (pin "1") (pinfunction "1_1") (pintype "passive"))
      (node (ref "R17") (pin "2") (pinfunction "2_2") (pintype "passive"))
    )
    (net (code "15") (name "/LED2") (class "Default")
      (node (ref "IC1") (pin "43") (pinfunction "PGED2/ASDA2/RP37/RB5_43") (pintype "bidirectional"))
      (node (ref "J20") (pin "2") (pinfunction "2_2") (pintype "passive"))
      (node (ref "R18") (pin "2") (pinfunction "2_2") (pintype "passive"))
    )
    (net (code "16") (name "/LED3") (class "Default")
      (node (ref "IC1") (pin "44") (pinfunction "PGEC2/ASCL2/RP38/PMCS2/RB6_44") (pintype "bidirectional"))
      (node (ref "J20") (pin "3") (pinfunction "3_3") (pintype "passive"))
      (node (ref "R19") (pin "2") (pinfunction "2_2") (pintype "passive"))
    )
    (net (code "17") (name "/LED4") (class "Default")
      (node (ref "IC1") (pin "49") (pinfunction "TMS/OA5IN-/AN27/C5IN4-/RP41/RB9_49") (pintype "bidirectional"))
      (node (ref "J20") (pin "4") (pinfunction "4_4") (pintype "passive"))
      (node (ref "R20") (pin "2") (pinfunction "2_2") (pintype "passive"))
    )
    (net (code "18") (name "/LED5") (class "Default")
      (node (ref "IC1") (pin "53") (pinfunction "RP69/PMRD/RD5_53") (pintype "bidirectional"))
      (node (ref "J21") (pin "1") (pinfunction "1_1") (pintype "passive"))
      (node (ref "R21") (pin "2") (pinfunction "2_2") (pintype "passive"))
    )
    (net (code "19") (name "/LED6") (class "Default")
      (node (ref "IC1") (pin "54") (pinfunction "RP70/RD6_54") (pintype "bidirectional"))
      (node (ref "J21") (pin "2") (pinfunction "2_2") (pintype "passive"))
      (node (ref "R22") (pin "2") (pinfunction "2_2") (pintype "passive"))
    )
    (net (code "20") (name "/LED7") (class "Default")
      (node (ref "IC1") (pin "58") (pinfunction "RPI96/RF0_58") (pintype "bidirectional"))
      (node (ref "J21") (pin "3") (pinfunction "3_3") (pintype "passive"))
      (node (ref "R23") (pin "2") (pinfunction "2_2") (pintype "passive"))
    )
    (net (code "21") (name "/LED8") (class "Default")
      (node (ref "IC1") (pin "59") (pinfunction "RP97/RF1_59") (pintype "bidirectional"))
      (node (ref "J21") (pin "4") (pinfunction "4_4") (pintype "passive"))
      (node (ref "R24") (pin "2") (pinfunction "2_2") (pintype "passive"))
    )
    (net (code "22") (name "/MISO") (class "Default")
      (node (ref "IC1") (pin "34") (pinfunction "AN28/SDI1/RPI25/RA9_34") (pintype "bidirectional"))
      (node (ref "J4") (pin "6") (pinfunction "6_6") (pintype "passive"))
      (node (ref "JP4") (pin "2") (pinfunction "2_2") (pintype "passive"))
      (node (ref "U3") (pin "10") (pinfunction "B4_10") (pintype "bidirectional"))
    )
    (net (code "23") (name "/MOSI") (class "Default")
      (node (ref "IC1") (pin "33") (pinfunction "OA5IN+/AN24/C5IN3-/C5IN1+/SDO1/RP20/T1CK/RA4_33") (pintype "bidirectional"))
      (node (ref "J4") (pin "5") (pinfunction "5_5") (pintype "passive"))
      (node (ref "JP3") (pin "2") (pinfunction "2_2") (pintype "passive"))
      (node (ref "U3") (pin "11") (pinfunction "B3_11") (pintype "bidirectional"))
    )
    (net (code "24") (name "/MUX1_SC0") (class "Default")
      (node (ref "J2") (pin "5") (pinfunction "5_5") (pintype "passive"))
      (node (ref "R30") (pin "2") (pinfunction "2_2") (pintype "passive"))
      (node (ref "U1") (pin "6") (pinfunction "SC0_6") (pintype "passive"))
    )
    (net (code "25") (name "/MUX1_SC1") (class "Default")
      (node (ref "J5") (pin "5") (pinfunction "5_5") (pintype "passive"))
      (node (ref "R32") (pin "2") (pinfunction "2_2") (pintype "passive"))
      (node (ref "U1") (pin "9") (pinfunction "SC1_9") (pintype "passive"))
    )
    (net (code "26") (name "/MUX1_SC2") (class "Default")
      (node (ref "J6") (pin "5") (pinfunction "5_5") (pintype "passive"))
      (node (ref "R34") (pin "2") (pinfunction "2_2") (pintype "passive"))
      (node (ref "U1") (pin "13") (pinfunction "SC2_13") (pintype "passive"))
    )
    (net (code "27") (name "/MUX1_SC3") (class "Default")
      (node (ref "J7") (pin "5") (pinfunction "5_5") (pintype "passive"))
      (node (ref "R36") (pin "2") (pinfunction "2_2") (pintype "passive"))
      (node (ref "U1") (pin "16") (pinfunction "SC3_16") (pintype "passive"))
    )
    (net (code "28") (name "/MUX1_SD0") (class "Default")
      (node (ref "J2") (pin "4") (pinfunction "4_4") (pintype "passive"))
      (node (ref "R29") (pin "2") (pinfunction "2_2") (pintype "passive"))
      (node (ref "U1") (pin "5") (pinfunction "SD0_5") (pintype "passive"))
    )
    (net (code "29") (name "/MUX1_SD1") (class "Default")
      (node (ref "J5") (pin "4") (pinfunction "4_4") (pintype "passive"))
      (node (ref "R31") (pin "2") (pinfunction "2_2") (pintype "passive"))
      (node (ref "U1") (pin "8") (pinfunction "SD1_8") (pintype "passive"))
    )
    (net (code "30") (name "/MUX1_SD2") (class "Default")
      (node (ref "J6") (pin "4") (pinfunction "4_4") (pintype "passive"))
      (node (ref "R33") (pin "2") (pinfunction "2_2") (pintype "passive"))
      (node (ref "U1") (pin "12") (pinfunction "SD2_12") (pintype "passive"))
    )
    (net (code "31") (name "/MUX1_SD3") (class "Default")
      (node (ref "J7") (pin "4") (pinfunction "4_4") (pintype "passive"))
      (node (ref "R35") (pin "2") (pinfunction "2_2") (pintype "passive"))
      (node (ref "U1") (pin "15") (pinfunction "SD3_15") (pintype "passive"))
    )
    (net (code "32") (name "/MUX2_SC0") (class "Default")
      (node (ref "J8") (pin "5") (pinfunction "5_5") (pintype "passive"))
      (node (ref "R38") (pin "2") (pinfunction "2_2") (pintype "passive"))
      (node (ref "U2") (pin "6") (pinfunction "SC0_6") (pintype "passive"))
    )
    (net (code "33") (name "/MUX2_SC1") (class "Default")
      (node (ref "J9") (pin "5") (pinfunction "5_5") (pintype "passive"))
      (node (ref "R40") (pin "2") (pinfunction "2_2") (pintype "passive"))
      (node (ref "U2") (pin "9") (pinfunction "SC1_9") (pintype "passive"))
    )
    (net (code "34") (name "/MUX2_SC2") (class "Default")
      (node (ref "J10") (pin "5") (pinfunction "5_5") (pintype "passive"))
      (node (ref "R42") (pin "2") (pinfunction "2_2") (pintype "passive"))
      (node (ref "U2") (pin "13") (pinfunction "SC2_13") (pintype "passive"))
    )
    (net (code "35") (name "/MUX2_SC3") (class "Default")
      (node (ref "J11") (pin "5") (pinfunction "5_5") (pintype "passive"))
      (node (ref "R44") (pin "2") (pinfunction "2_2") (pintype "passive"))
      (node (ref "U2") (pin "16") (pinfunction "SC3_16") (pintype "passive"))
      (node (ref "U8") (pin "4") (pinfunction "SCL/SPC_4") (pintype "input"))
    )
    (net (code "36") (name "/MUX2_SD0") (class "Default")
      (node (ref "J8") (pin "4") (pinfunction "4_4") (pintype "passive"))
      (node (ref "R37") (pin "2") (pinfunction "2_2") (pintype "passive"))
      (node (ref "U2") (pin "5") (pinfunction "SD0_5") (pintype "passive"))
    )
    (net (code "37") (name "/MUX2_SD1") (class "Default")
      (node (ref "J9") (pin "4") (pinfunction "4_4") (pintype "passive"))
      (node (ref "R39") (pin "2") (pinfunction "2_2") (pintype "passive"))
      (node (ref "U2") (pin "8") (pinfunction "SD1_8") (pintype "passive"))
    )
    (net (code "38") (name "/MUX2_SD2") (class "Default")
      (node (ref "J10") (pin "4") (pinfunction "4_4") (pintype "passive"))
      (node (ref "R41") (pin "2") (pinfunction "2_2") (pintype "passive"))
      (node (ref "U2") (pin "12") (pinfunction "SD2_12") (pintype "passive"))
    )
    (net (code "39") (name "/MUX2_SD3") (class "Default")
      (node (ref "J11") (pin "4") (pinfunction "4_4") (pintype "passive"))
      (node (ref "R43") (pin "2") (pinfunction "2_2") (pintype "passive"))
      (node (ref "U2") (pin "15") (pinfunction "SD3_15") (pintype "passive"))
      (node (ref "U8") (pin "6") (pinfunction "SDA/SDI/SDO_6") (pintype "bidirectional"))
    )
    (net (code "40") (name "/OSC1") (class "Default")
      (node (ref "C15") (pin "1") (pinfunction "1_1") (pintype "passive"))
      (node (ref "IC1") (pin "39") (pinfunction "AN49/OSC1/CLKI/RPI60/RC12_39") (pintype "bidirectional"))
      (node (ref "R70") (pin "1") (pinfunction "1_1") (pintype "passive"))
      (node (ref "U$3") (pin "3") (pinfunction "3_3") (pintype "bidirectional"))
    )
    (net (code "41") (name "/OSC2") (class "Default")
      (node (ref "C14") (pin "1") (pinfunction "1_1") (pintype "passive"))
      (node (ref "IC1") (pin "40") (pinfunction "OSC2/CLKO/RPI63/RC15_40") (pintype "bidirectional"))
      (node (ref "R70") (pin "2") (pinfunction "2_2") (pintype "passive"))
      (node (ref "U$3") (pin "1") (pinfunction "1_1") (pintype "bidirectional"))
    )
    (net (code "42") (name "/PGEC1") (class "Default")
      (node (ref "IC1") (pin "17") (pinfunction "PGEC1/OA1IN+/AN4/C1IN3-/C1IN1+/C2IN3-/RPI34/RB2_17") (pintype "bidirectional"))
      (node (ref "J12") (pin "5") (pinfunction "5_5") (pintype "passive"))
    )
    (net (code "43") (name "/PGED1") (class "Default")
      (node (ref "IC1") (pin "18") (pinfunction "PGED1/OA1IN-/AN5/C1IN1-/(CTMUC)/RP35/RTCC/RB3_18") (pintype "bidirectional"))
      (node (ref "J12") (pin "4") (pinfunction "4_4") (pintype "passive"))
    )
    (net (code "44") (name "/PWM1H") (class "Default")
      (node (ref "IC1") (pin "2") (pinfunction "RPI46/PWM1H/T3CK/T7CK/PMD6/RB14_2") (pintype "bidirectional"))
      (node (ref "J23") (pin "1") (pinfunction "1_1") (pintype "passive"))
    )
    (net (code "45") (name "/PWM1L") (class "Default")
      (node (ref "IC1") (pin "3") (pinfunction "RPI47/PWM1L/T5CK/T6CK/PMD7/RB15_3") (pintype "bidirectional"))
      (node (ref "J18") (pin "1") (pinfunction "1_1") (pintype "passive"))
    )
    (net (code "46") (name "/PWM2H") (class "Default")
      (node (ref "IC1") (pin "62") (pinfunction "RPI44/PWM2H/PMD2/RB12_62") (pintype "bidirectional"))
      (node (ref "J23") (pin "2") (pinfunction "2_2") (pintype "passive"))
    )
    (net (code "47") (name "/PWM2L") (class "Default")
      (node (ref "IC1") (pin "63") (pinfunction "RPI45/PWM2L/CTPLS/PMD3/RB13_63") (pintype "bidirectional"))
      (node (ref "J18") (pin "2") (pinfunction "2_2") (pintype "passive"))
    )
    (net (code "48") (name "/PWM3H") (class "Default")
      (node (ref "IC1") (pin "60") (pinfunction "RP42/PWM3H/PMD0/RB10_60") (pintype "bidirectional"))
      (node (ref "J23") (pin "3") (pinfunction "3_3") (pintype "passive"))
    )
    (net (code "49") (name "/PWM3L") (class "Default")
      (node (ref "IC1") (pin "61") (pinfunction "RP43/PWM3L/PMD1/RB11_61") (pintype "bidirectional"))
      (node (ref "J18") (pin "3") (pinfunction "3_3") (pintype "passive"))
    )
    (net (code "50") (name "/PWM4H") (class "Default")
      (node (ref "IC1") (pin "64") (pinfunction "TDO/PWM4H/PMD4/RA10_64") (pintype "bidirectional"))
      (node (ref "J24") (pin "1") (pinfunction "1_1") (pintype "passive"))
    )
    (net (code "51") (name "/PWM4L") (class "Default")
      (node (ref "IC1") (pin "1") (pinfunction "TDI/PWM4L/PMD5/RA7_1") (pintype "bidirectional"))
      (node (ref "J22") (pin "1") (pinfunction "1_1") (pintype "passive"))
    )
    (net (code "52") (name "/PWM5H") (class "Default")
      (node (ref "IC1") (pin "52") (pinfunction "RP56/PWM5H/PMWR/RC8_52") (pintype "bidirectional"))
      (node (ref "J24") (pin "2") (pinfunction "2_2") (pintype "passive"))
    )
    (net (code "53") (name "/PWM5L") (class "Default")
      (node (ref "IC1") (pin "55") (pinfunction "RP57/PWM5L/RC9_55") (pintype "bidirectional"))
      (node (ref "J22") (pin "2") (pinfunction "2_2") (pintype "passive"))
    )
    (net (code "54") (name "/PWM6H") (class "Default")
      (node (ref "IC1") (pin "50") (pinfunction "RP54/PWM6H/RC6_50") (pintype "bidirectional"))
      (node (ref "J24") (pin "3") (pinfunction "3_3") (pintype "passive"))
    )
    (net (code "55") (name "/PWM6L") (class "Default")
      (node (ref "IC1") (pin "51") (pinfunction "RP55/PWM6L/PMBE/RC7_51") (pintype "bidirectional"))
      (node (ref "J22") (pin "3") (pinfunction "3_3") (pintype "passive"))
    )
    (net (code "56") (name "/RGB_DIN") (class "Default")
      (node (ref "IC1") (pin "11") (pinfunction "AN10/RPI28/RA12_11") (pintype "bidirectional"))
      (node (ref "J13") (pin "3") (pinfunction "3_3") (pintype "passive"))
    )
    (net (code "57") (name "/SCK") (class "Default")
      (node (ref "IC1") (pin "35") (pinfunction "AN29/SCK1/RPI51/RC3_35") (pintype "bidirectional"))
      (node (ref "J4") (pin "4") (pinfunction "4_4") (pintype "passive"))
      (node (ref "JP2") (pin "2") (pinfunction "2_2") (pintype "passive"))
      (node (ref "U3") (pin "12") (pinfunction "B2_12") (pintype "bidirectional"))
    )
    (net (code "58") (name "/SCL1") (class "Default")
      (node (ref "IC1") (pin "37") (pinfunction "AN31/SCL1/RPI53/RC5_37") (pintype "bidirectional"))
      (node (ref "J1") (pin "5") (pinfunction "5_5") (pintype "passive"))
      (node (ref "R28") (pin "2") (pinfunction "2_2") (pintype "passive"))
      (node (ref "U1") (pin "18") (pinfunction "SCL_18") (pintype "passive"))
      (node (ref "U2") (pin "18") (pinfunction "SCL_18") (pintype "passive"))
    )
    (net (code "59") (name "/SDA1") (class "Default")
      (node (ref "IC1") (pin "36") (pinfunction "AN30/SDA1/RPI52/RC4_36") (pintype "bidirectional"))
      (node (ref "J1") (pin "4") (pinfunction "4_4") (pintype "passive"))
      (node (ref "R27") (pin "2") (pinfunction "2_2") (pintype "passive"))
      (node (ref "U1") (pin "19") (pinfunction "SDA_19") (pintype "passive"))
      (node (ref "U2") (pin "19") (pinfunction "SDA_19") (pintype "passive"))
    )
    (net (code "60") (name "/SD_CD") (class "Default")
      (node (ref "J26") (pin "CD1") (pinfunction "CD1_CD1") (pintype "bidirectional"))
      (node (ref "JP5") (pin "1") (pinfunction "1_1") (pintype "passive"))
      (node (ref "U3") (pin "6") (pinfunction "NC_2_6") (pintype "passive"))
    )
    (net (code "61") (name "/SD_MISO") (class "Default")
      (node (ref "J26") (pin "DO") (pinfunction "DO_DO") (pintype "bidirectional"))
      (node (ref "JP4") (pin "1") (pinfunction "1_1") (pintype "passive"))
      (node (ref "U3") (pin "5") (pinfunction "A4_5") (pintype "bidirectional"))
    )
    (net (code "62") (name "/SD_MOSI") (class "Default")
      (node (ref "J26") (pin "DI") (pinfunction "DI_DI") (pintype "bidirectional"))
      (node (ref "JP3") (pin "1") (pinfunction "1_1") (pintype "passive"))
      (node (ref "U3") (pin "4") (pinfunction "A3_4") (pintype "bidirectional"))
    )
    (net (code "63") (name "/SD_SCK") (class "Default")
      (node (ref "J26") (pin "SCLK") (pinfunction "SCK_SCLK") (pintype "bidirectional"))
      (node (ref "JP2") (pin "1") (pinfunction "1_1") (pintype "passive"))
      (node (ref "U3") (pin "3") (pinfunction "A2_3") (pintype "bidirectional"))
    )
    (net (code "64") (name "/SD_~{SS}") (class "Default")
      (node (ref "J26") (pin "CS") (pinfunction "~{CS}_CS") (pintype "bidirectional"))
      (node (ref "JP1") (pin "1") (pinfunction "1_1") (pintype "passive"))
      (node (ref "U3") (pin "2") (pinfunction "A1_2") (pintype "bidirectional"))
    )
    (net (code "65") (name "/U1CTS") (class "Default")
      (node (ref "IC1") (pin "24") (pinfunction "AN11/C1IN2-/U1CTS/FLT4/PMA12/RC11_24") (pintype "bidirectional"))
      (node (ref "J14") (pin "2") (pinfunction "2_2") (pintype "passive"))
    )
    (net (code "66") (name "/U1RX") (class "Default")
      (node (ref "IC1") (pin "22") (pinfunction "OA3IN-/AN7/C3IN1-/C4IN1-/RP49/RC1_22") (pintype "bidirectional"))
      (node (ref "J14") (pin "4") (pinfunction "4_4") (pintype "passive"))
    )
    (net (code "67") (name "/U1TX") (class "Default")
      (node (ref "IC1") (pin "21") (pinfunction "OA3OUT/AN6/C3IN4-/C4IN1+/RP48/OCFB/RC0_21") (pintype "bidirectional"))
      (node (ref "J14") (pin "5") (pinfunction "5_5") (pintype "passive"))
    )
    (net (code "68") (name "/USBDM") (class "Default")
      (node (ref "R47") (pin "2") (pinfunction "2_2") (pintype "passive"))
    )
    (net (code "69") (name "/USBDP") (class "Default")
      (node (ref "R48") (pin "2") (pinfunction "2_2") (pintype "passive"))
    )
    (net (code "70") (name "/VBATT") (class "Default")
      (node (ref "C9") (pin "1") (pinfunction "1_1") (pintype "passive"))
      (node (ref "R57") (pin "1") (pinfunction "1_1") (pintype "passive"))
      (node (ref "R59") (pin "1") (pinfunction "1_1") (pintype "passive"))
      (node (ref "U4") (pin "5") (pinfunction "VIN_5") (pintype "power_in"))
      (node (ref "U4") (pin "8") (pinfunction "VINA_8") (pintype "power_in"))
    )
    (net (code "71") (name "/VCAP") (class "Default")
      (node (ref "C11") (pin "1") (pinfunction "1_1") (pintype "passive"))
      (node (ref "IC1") (pin "56") (pinfunction "VCAP_56") (pintype "bidirectional"))
    )
    (net (code "72") (name "/VCC_USB") (class "Default")
      (node (ref "C7") (pin "1") (pinfunction "1_1") (pintype "passive"))
      (node (ref "D9") (pin "A") (pinfunction "A_A") (pintype "passive"))
      (node (ref "J15") (pin "2") (pinfunction "2_2") (pintype "passive"))
      (node (ref "J17") (pin "1") (pinfunction "1_1") (pintype "bidirectional"))
      (node (ref "U5") (pin "4") (pinfunction "VDD_4") (pintype "passive"))
    )
    (net (code "73") (name "/V_BATT") (class "Default")
      (node (ref "C8") (pin "1") (pinfunction "1_1") (pintype "passive"))
      (node (ref "J16") (pin "2") (pinfunction "2_2") (pintype "passive"))
      (node (ref "U5") (pin "3") (pinfunction "VBAT_3") (pintype "passive"))
    )
    (net (code "74") (name "/~{MCLR}") (class "Default")
      (node (ref "IC1") (pin "7") (pinfunction "~{MCLR}_7") (pintype "bidirectional"))
      (node (ref "J12") (pin "1") (pinfunction "1_1") (pintype "passive"))
      (node (ref "R1") (pin "1") (pinfunction "1_1") (pintype "passive"))
    )
    (net (code "75") (name "/~{MUX1_INT0}") (class "Default")
      (node (ref "J2") (pin "3") (pinfunction "3_3") (pintype "passive"))
      (node (ref "R61") (pin "2") (pinfunction "2_2") (pintype "passive"))
      (node (ref "U1") (pin "4") (pinfunction "~{INT0}_4") (pintype "passive"))
    )
    (net (code "76") (name "/~{MUX1_INT1}") (class "Default")
      (node (ref "J5") (pin "3") (pinfunction "3_3") (pintype "passive"))
      (node (ref "R62") (pin "2") (pinfunction "2_2") (pintype "passive"))
      (node (ref "U1") (pin "7") (pinfunction "~{INT1}_7") (pintype "passive"))
    )
    (net (code "77") (name "/~{MUX1_INT2}") (class "Default")
      (node (ref "J6") (pin "3") (pinfunction "3_3") (pintype "passive"))
      (node (ref "R63") (pin "2") (pinfunction "2_2") (pintype "passive"))
      (node (ref "U1") (pin "11") (pinfunction "~{INT2}_11") (pintype "passive"))
    )
    (net (code "78") (name "/~{MUX1_INT3}") (class "Default")
      (node (ref "J7") (pin "3") (pinfunction "3_3") (pintype "passive"))
      (node (ref "R64") (pin "2") (pinfunction "2_2") (pintype "passive"))
      (node (ref "U1") (pin "14") (pinfunction "~{INT3}_14") (pintype "passive"))
    )
    (net (code "79") (name "/~{MUX2_INT0}") (class "Default")
      (node (ref "J8") (pin "3") (pinfunction "3_3") (pintype "passive"))
      (node (ref "R65") (pin "2") (pinfunction "2_2") (pintype "passive"))
      (node (ref "U2") (pin "4") (pinfunction "~{INT0}_4") (pintype "passive"))
    )
    (net (code "80") (name "/~{MUX2_INT1}") (class "Default")
      (node (ref "J9") (pin "3") (pinfunction "3_3") (pintype "passive"))
      (node (ref "R66") (pin "2") (pinfunction "2_2") (pintype "passive"))
      (node (ref "U2") (pin "7") (pinfunction "~{INT1}_7") (pintype "passive"))
    )
    (net (code "81") (name "/~{MUX2_INT2}") (class "Default")
      (node (ref "J10") (pin "3") (pinfunction "3_3") (pintype "passive"))
      (node (ref "R67") (pin "2") (pinfunction "2_2") (pintype "passive"))
      (node (ref "U2") (pin "11") (pinfunction "~{INT2}_11") (pintype "passive"))
    )
    (net (code "82") (name "/~{MUX2_INT3}") (class "Default")
      (node (ref "J11") (pin "3") (pinfunction "3_3") (pintype "passive"))
      (node (ref "R68") (pin "2") (pinfunction "2_2") (pintype "passive"))
      (node (ref "U2") (pin "14") (pinfunction "~{INT3}_14") (pintype "passive"))
      (node (ref "U8") (pin "11") (pinfunction "INT_1_11") (pintype "output"))
    )
    (net (code "83") (name "/~{RGB1_EN}") (class "Default")
      (node (ref "IC1") (pin "4") (pinfunction "AN19/RP118/PMA5/RG6_4") (pintype "bidirectional"))
      (node (ref "J25") (pin "1") (pinfunction "1_1") (pintype "passive"))
    )
    (net (code "84") (name "/~{RGB2_EN}") (class "Default")
      (node (ref "IC1") (pin "5") (pinfunction "AN18/ASCL1/RPI119/PMA4/RG7_5") (pintype "bidirectional"))
      (node (ref "J25") (pin "2") (pinfunction "2_2") (pintype "passive"))
    )
    (net (code "85") (name "/~{RGB3_EN}") (class "Default")
      (node (ref "IC1") (pin "6") (pinfunction "AN17/ASDA1/RP120/PMA3/RG8_6") (pintype "bidirectional"))
      (node (ref "J25") (pin "3") (pinfunction "3_3") (pintype "passive"))
    )
    (net (code "86") (name "/~{SS}") (class "Default")
      (node (ref "IC1") (pin "15") (pinfunction "PGED3/VREF-/OA2IN-/AN2/C2IN1-/~{SS1}/RPI32/CTED2/RB0_15") (pintype "bidirectional"))
      (node (ref "J4") (pin "3") (pinfunction "3_3") (pintype "passive"))
      (node (ref "JP1") (pin "2") (pinfunction "2_2") (pintype "passive"))
      (node (ref "U3") (pin "13") (pinfunction "B1_13") (pintype "bidirectional"))
    )
    (net (code "87") (name "/~{U1RTS}") (class "Default")
      (node (ref "IC1") (pin "23") (pinfunction "OA3IN+/AN8/C3IN3-/C3IN1+/RPI50/~{U1RTS}/BCLK1/FLT3/RC2_23") (pintype "bidirectional"))
      (node (ref "J14") (pin "6") (pinfunction "6_6") (pintype "passive"))
    )
    (net (code "88") (name "GND") (class "Default")
      (node (ref "C1") (pin "2") (pinfunction "2_2") (pintype "passive"))
      (node (ref "C10") (pin "2") (pinfunction "2_2") (pintype "passive"))
      (node (ref "C11") (pin "2") (pinfunction "2_2") (pintype "passive"))
      (node (ref "C12") (pin "2") (pinfunction "2_2") (pintype "passive"))
      (node (ref "C13") (pin "-") (pinfunction "-_-") (pintype "passive"))
      (node (ref "C14") (pin "2") (pinfunction "2_2") (pintype "passive"))
      (node (ref "C15") (pin "2") (pinfunction "2_2") (pintype "passive"))
      (node (ref "C2") (pin "2") (pinfunction "2_2") (pintype "passive"))
      (node (ref "C3") (pin "2") (pinfunction "2_2") (pintype "passive"))
      (node (ref "C4") (pin "2") (pinfunction "2_2") (pintype "passive"))
      (node (ref "C5") (pin "2") (pinfunction "2_2") (pintype "passive"))
      (node (ref "C6") (pin "2") (pinfunction "2_2") (pintype "passive"))
      (node (ref "C7") (pin "2") (pinfunction "2_2") (pintype "passive"))
      (node (ref "C8") (pin "2") (pinfunction "2_2") (pintype "passive"))
      (node (ref "C9") (pin "2") (pinfunction "2_2") (pintype "passive"))
      (node (ref "D1") (pin "C") (pinfunction "C_C") (pintype "passive"))
      (node (ref "D2") (pin "C") (pinfunction "C_C") (pintype "passive"))
      (node (ref "D3") (pin "C") (pinfunction "C_C") (pintype "passive"))
      (node (ref "D4") (pin "C") (pinfunction "C_C") (pintype "passive"))
      (node (ref "D5") (pin "C") (pinfunction "C_C") (pintype "passive"))
      (node (ref "D6") (pin "C") (pinfunction "C_C") (pintype "passive"))
      (node (ref "D7") (pin "C") (pinfunction "C_C") (pintype "passive"))
      (node (ref "D8") (pin "C") (pinfunction "C_C") (pintype "passive"))
      (node (ref "H1") (pin "B3,0") (pinfunction "MOUNT_B3,0") (pintype "passive"))
      (node (ref "H2") (pin "B3,0") (pinfunction "MOUNT_B3,0") (pintype "passive"))
      (node (ref "H3") (pin "B3,0") (pinfunction "MOUNT_B3,0") (pintype "passive"))
      (node (ref "H4") (pin "B3,0") (pinfunction "MOUNT_B3,0") (pintype "passive"))
      (node (ref "IC1") (pin "20") (pinfunction "AVSS_20") (pintype "bidirectional"))
      (node (ref "IC1") (pin "25") (pinfunction "VSS_2_25") (pintype "bidirectional"))
      (node (ref "IC1") (pin "41") (pinfunction "VSS_3_41") (pintype "bidirectional"))
      (node (ref "IC1") (pin "9") (pinfunction "VSS_1_9") (pintype "bidirectional"))
      (node (ref "J1") (pin "2") (pinfunction "2_2") (pintype "passive"))
      (node (ref "J10") (pin "2") (pinfunction "2_2") (pintype "passive"))
      (node (ref "J11") (pin "2") (pinfunction "2_2") (pintype "passive"))
      (node (ref "J12") (pin "3") (pinfunction "3_3") (pintype "passive"))
      (node (ref "J13") (pin "1") (pinfunction "1_1") (pintype "passive"))
      (node (ref "J14") (pin "1") (pinfunction "1_1") (pintype "passive"))
      (node (ref "J15") (pin "1") (pinfunction "1_1") (pintype "passive"))
      (node (ref "J16") (pin "1") (pinfunction "1_1") (pintype "passive"))
      (node (ref "J17") (pin "5") (pinfunction "5_5") (pintype "bidirectional"))
      (node (ref "J17") (pin "P1") (pinfunction "P1_P1") (pintype "bidirectional"))
      (node (ref "J17") (pin "P2") (pinfunction "P2_P2") (pintype "bidirectional"))
      (node (ref "J17") (pin "P3") (pinfunction "P3_P3") (pintype "bidirectional"))
      (node (ref "J17") (pin "P4") (pinfunction "P4_P4") (pintype "bidirectional"))
      (node (ref "J17") (pin "P5") (pinfunction "P5_P5") (pintype "bidirectional"))
      (node (ref "J17") (pin "P6") (pinfunction "P6_P6") (pintype "bidirectional"))
      (node (ref "J19") (pin "1") (pinfunction "1_1") (pintype "passive"))
      (node (ref "J2") (pin "2") (pinfunction "2_2") (pintype "passive"))
      (node (ref "J26") (pin "GND") (pinfunction "GND_GND") (pintype "bidirectional"))
      (node (ref "J26") (pin "GND1") (pinfunction "SHIELD_GND1") (pintype "bidirectional"))
      (node (ref "J26") (pin "GND3") (pinfunction "SHIELD_GND3") (pintype "bidirectional"))
      (node (ref "J4") (pin "2") (pinfunction "2_2") (pintype "passive"))
      (node (ref "J5") (pin "2") (pinfunction "2_2") (pintype "passive"))
      (node (ref "J6") (pin "2") (pinfunction "2_2") (pintype "passive"))
      (node (ref "J7") (pin "2") (pinfunction "2_2") (pintype "passive"))
      (node (ref "J8") (pin "2") (pinfunction "2_2") (pintype "passive"))
      (node (ref "J9") (pin "2") (pinfunction "2_2") (pintype "passive"))
      (node (ref "R10") (pin "1") (pinfunction "1_1") (pintype "passive"))
      (node (ref "R12") (pin "1") (pinfunction "1_1") (pintype "passive"))
      (node (ref "R14") (pin "1") (pinfunction "1_1") (pintype "passive"))
      (node (ref "R16") (pin "1") (pinfunction "1_1") (pintype "passive"))
      (node (ref "R4") (pin "1") (pinfunction "1_1") (pintype "passive"))
      (node (ref "R46") (pin "1") (pinfunction "1_1") (pintype "passive"))
      (node (ref "R50") (pin "1") (pinfunction "1_1") (pintype "passive"))
      (node (ref "R58") (pin "1") (pinfunction "1_1") (pintype "passive"))
      (node (ref "R6") (pin "1") (pinfunction "1_1") (pintype "passive"))
      (node (ref "R60") (pin "1") (pinfunction "1_1") (pintype "passive"))
      (node (ref "R8") (pin "1") (pinfunction "1_1") (pintype "passive"))
      (node (ref "S1") (pin "A2") (pinfunction "1_A2") (pintype "passive"))
      (node (ref "U$3") (pin "2") (pinfunction "GND_2") (pintype "bidirectional"))
      (node (ref "U$3") (pin "4") (pinfunction "GND_4") (pintype "bidirectional"))
      (node (ref "U1") (pin "10") (pinfunction "VSS_10") (pintype "passive"))
      (node (ref "U2") (pin "10") (pinfunction "VSS_10") (pintype "passive"))
      (node (ref "U3") (pin "7") (pinfunction "GND_7") (pintype "power_in"))
      (node (ref "U4") (pin "11") (pinfunction "EPAD_11") (pintype "passive"))
      (node (ref "U4") (pin "3") (pinfunction "PGND_3") (pintype "passive"))
      (node (ref "U4") (pin "9") (pinfunction "GND_9") (pintype "passive"))
      (node (ref "U5") (pin "2") (pinfunction "VSS_2") (pintype "passive"))
      (node (ref "U8") (pin "10") (pinfunction "GND_10") (pintype "power_in"))
      (node (ref "U8") (pin "12") (pinfunction "GND_12") (pintype "power_in"))
      (node (ref "U8") (pin "13") (pinfunction "GND_13") (pintype "power_in"))
      (node (ref "U8") (pin "16") (pinfunction "GND_16") (pintype "power_in"))
      (node (ref "U8") (pin "5") (pinfunction "GND_5") (pintype "power_in"))
    )
    (net (code "89") (name "Net-(D1-PadA)") (class "Default")
      (node (ref "D1") (pin "A") (pinfunction "A_A") (pintype "passive"))
      (node (ref "R17") (pin "1") (pinfunction "1_1") (pintype "passive"))
    )
    (net (code "90") (name "Net-(D2-PadA)") (class "Default")
      (node (ref "D2") (pin "A") (pinfunction "A_A") (pintype "passive"))
      (node (ref "R18") (pin "1") (pinfunction "1_1") (pintype "passive"))
    )
    (net (code "91") (name "Net-(D3-PadA)") (class "Default")
      (node (ref "D3") (pin "A") (pinfunction "A_A") (pintype "passive"))
      (node (ref "R19") (pin "1") (pinfunction "1_1") (pintype "passive"))
    )
    (net (code "92") (name "Net-(D4-PadA)") (class "Default")
      (node (ref "D4") (pin "A") (pinfunction "A_A") (pintype "passive"))
      (node (ref "R20") (pin "1") (pinfunction "1_1") (pintype "passive"))
    )
    (net (code "93") (name "Net-(D5-PadA)") (class "Default")
      (node (ref "D5") (pin "A") (pinfunction "A_A") (pintype "passive"))
      (node (ref "R21") (pin "1") (pinfunction "1_1") (pintype "passive"))
    )
    (net (code "94") (name "Net-(D6-PadA)") (class "Default")
      (node (ref "D6") (pin "A") (pinfunction "A_A") (pintype "passive"))
      (node (ref "R22") (pin "1") (pinfunction "1_1") (pintype "passive"))
    )
    (net (code "95") (name "Net-(D7-PadA)") (class "Default")
      (node (ref "D7") (pin "A") (pinfunction "A_A") (pintype "passive"))
      (node (ref "R23") (pin "1") (pinfunction "1_1") (pintype "passive"))
    )
    (net (code "96") (name "Net-(D8-PadA)") (class "Default")
      (node (ref "D8") (pin "A") (pinfunction "A_A") (pintype "passive"))
      (node (ref "R24") (pin "1") (pinfunction "1_1") (pintype "passive"))
    )
    (net (code "97") (name "Net-(D9-PadC)") (class "Default")
      (node (ref "D9") (pin "C") (pinfunction "C_C") (pintype "passive"))
      (node (ref "R45") (pin "1") (pinfunction "1_1") (pintype "passive"))
    )
    (net (code "98") (name "Net-(J17-Pad2)") (class "Default")
      (node (ref "J17") (pin "2") (pinfunction "2_2") (pintype "bidirectional"))
      (node (ref "R47") (pin "1") (pinfunction "1_1") (pintype "passive"))
    )
    (net (code "99") (name "Net-(J17-Pad3)") (class "Default")
      (node (ref "J17") (pin "3") (pinfunction "3_3") (pintype "bidirectional"))
      (node (ref "R48") (pin "1") (pinfunction "1_1") (pintype "passive"))
    )
    (net (code "100") (name "Net-(S1-2)") (class "Default")
      (node (ref "C1") (pin "1") (pinfunction "1_1") (pintype "passive"))
      (node (ref "R1") (pin "2") (pinfunction "2_2") (pintype "passive"))
      (node (ref "R2") (pin "2") (pinfunction "2_2") (pintype "passive"))
      (node (ref "S1") (pin "B2") (pinfunction "2_B2") (pintype "passive"))
    )
    (net (code "101") (name "Net-(U4-FB)") (class "Default")
      (node (ref "R49") (pin "1") (pinfunction "1_1") (pintype "passive"))
      (node (ref "R50") (pin "2") (pinfunction "2_2") (pintype "passive"))
      (node (ref "U4") (pin "10") (pinfunction "FB_10") (pintype "passive"))
    )
    (net (code "102") (name "Net-(U4-SW1)") (class "Default")
      (node (ref "U$1") (pin "2") (pinfunction "2_2") (pintype "passive"))
      (node (ref "U4") (pin "4") (pinfunction "SW1_4") (pintype "bidirectional"))
    )
    (net (code "103") (name "Net-(U4-SW2)") (class "Default")
      (node (ref "U$1") (pin "1") (pinfunction "1_1") (pintype "passive"))
      (node (ref "U4") (pin "2") (pinfunction "SW2_2") (pintype "bidirectional"))
    )
    (net (code "104") (name "Net-(U5-PROG)") (class "Default")
      (node (ref "R46") (pin "2") (pinfunction "2_2") (pintype "passive"))
      (node (ref "U5") (pin "5") (pinfunction "PROG_5") (pintype "passive"))
    )
    (net (code "105") (name "Net-(U5-STAT)") (class "Default")
      (node (ref "R45") (pin "2") (pinfunction "2_2") (pintype "passive"))
      (node (ref "U5") (pin "1") (pinfunction "STAT_1") (pintype "passive"))
    )
    (net (code "106") (name "Net-(U8-CS)") (class "Default")
      (node (ref "R69") (pin "1") (pinfunction "1_1") (pintype "passive"))
      (node (ref "U8") (pin "8") (pinfunction "CS_8") (pintype "input"))
    )
    (net (code "107") (name "unconnected-(IC1-AN9{slash}RPI27{slash}RA11-Pad12)") (class "Default")
      (node (ref "IC1") (pin "12") (pinfunction "AN9/RPI27/RA11_12") (pintype "bidirectional"))
    )
    (net (code "108") (name "unconnected-(IC1-AN12{slash}C2IN2-{slash}C5IN2-{slash}~{U2RTS}{slash}BCLK2{slash}FLT5{slash}PMA11{slash}RE12-Pad27)") (class "Default")
      (node (ref "IC1") (pin "27") (pinfunction "AN12/C2IN2-/C5IN2-/~{U2RTS}/BCLK2/FLT5/PMA11/RE12_27") (pintype "bidirectional"))
    )
    (net (code "109") (name "unconnected-(IC1-AN13{slash}C3IN2-{slash}~{U2CTS}{slash}FLT6{slash}PMA10{slash}RE13-Pad28)") (class "Default")
      (node (ref "IC1") (pin "28") (pinfunction "AN13/C3IN2-/~{U2CTS}/FLT6/PMA10/RE13_28") (pintype "bidirectional"))
    )
    (net (code "110") (name "unconnected-(IC1-AN14{slash}RPI94{slash}FLT7{slash}PMA1{slash}RE14-Pad29)") (class "Default")
      (node (ref "IC1") (pin "29") (pinfunction "AN14/RPI94/FLT7/PMA1/RE14_29") (pintype "bidirectional"))
    )
    (net (code "111") (name "unconnected-(IC1-AN15{slash}RPI95{slash}FLT8{slash}PMA0{slash}RE15-Pad30)") (class "Default")
      (node (ref "IC1") (pin "30") (pinfunction "AN15/RPI95/FLT8/PMA0/RE15_30") (pintype "bidirectional"))
    )
    (net (code "112") (name "unconnected-(IC1-AN16{slash}RPI121{slash}PMA2{slash}RG9-Pad8)") (class "Default")
      (node (ref "IC1") (pin "8") (pinfunction "AN16/RPI121/PMA2/RG9_8") (pintype "bidirectional"))
    )
    (net (code "113") (name "unconnected-(IC1-AN48{slash}CVREF2O{slash}RPI58{slash}PMCS1{slash}RC10-Pad45)") (class "Default")
      (node (ref "IC1") (pin "45") (pinfunction "AN48/CVREF2O/RPI58/PMCS1/RC10_45") (pintype "bidirectional"))
    )
    (net (code "114") (name "unconnected-(IC1-FLT32{slash}SCL2{slash}RP36{slash}PMA8{slash}RB4-Pad32)") (class "Default")
      (node (ref "IC1") (pin "32") (pinfunction "FLT32/SCL2/RP36/PMA8/RB4_32") (pintype "bidirectional"))
    )
    (net (code "115") (name "unconnected-(IC1-OA2IN+{slash}AN1{slash}C2IN1+{slash}RPI17{slash}RA1-Pad14)") (class "Default")
      (node (ref "IC1") (pin "14") (pinfunction "OA2IN+/AN1/C2IN1+/RPI17/RA1_14") (pintype "bidirectional"))
    )
    (net (code "116") (name "unconnected-(IC1-OA2OUT{slash}AN0{slash}C2IN4-{slash}C4IN3-{slash}RPI16{slash}RA0-Pad13)") (class "Default")
      (node (ref "IC1") (pin "13") (pinfunction "OA2OUT/AN0/C2IN4-/C4IN3-/RPI16/RA0_13") (pintype "bidirectional"))
    )
    (net (code "117") (name "unconnected-(IC1-OA5OUT{slash}AN25{slash}C5IN4-{slash}RP39{slash}INT0{slash}RB7-Pad46)") (class "Default")
      (node (ref "IC1") (pin "46") (pinfunction "OA5OUT/AN25/C5IN4-/RP39/INT0/RB7_46") (pintype "bidirectional"))
    )
    (net (code "118") (name "unconnected-(IC1-SDA2{slash}RPI24{slash}PMA9{slash}RA8-Pad31)") (class "Default")
      (node (ref "IC1") (pin "31") (pinfunction "SDA2/RPI24/PMA9/RA8_31") (pintype "bidirectional"))
    )
    (net (code "119") (name "unconnected-(IC1-SOSCI{slash}RPI61{slash}RC13-Pad47)") (class "Default")
      (node (ref "IC1") (pin "47") (pinfunction "SOSCI/RPI61/RC13_47") (pintype "bidirectional"))
    )
    (net (code "120") (name "unconnected-(IC1-TCK{slash}AN26{slash}CVREF1O{slash}SOSCO{slash}RP40{slash}T4CK{slash}RB8-Pad48)") (class "Default")
      (node (ref "IC1") (pin "48") (pinfunction "TCK/AN26/CVREF1O/SOSCO/RP40/T4CK/RB8_48") (pintype "bidirectional"))
    )
    (net (code "121") (name "unconnected-(J17-Pad4)") (class "Default")
      (node (ref "J17") (pin "4") (pinfunction "4_4") (pintype "bidirectional"))
    )
    (net (code "122") (name "unconnected-(J26-PadCD2)") (class "Default")
      (node (ref "J26") (pin "CD2") (pinfunction "CD2_CD2") (pintype "bidirectional"))
    )
    (net (code "123") (name "unconnected-(J26-RSV-PadRSV1)") (class "Default")
      (node (ref "J26") (pin "RSV1") (pinfunction "RSV_RSV1") (pintype "bidirectional"))
    )
    (net (code "124") (name "unconnected-(J26-RSV-PadRSV2)") (class "Default")
      (node (ref "J26") (pin "RSV2") (pinfunction "RSV_RSV2") (pintype "bidirectional"))
    )
    (net (code "125") (name "unconnected-(U1-~{INT}-Pad17)") (class "Default")
      (node (ref "U1") (pin "17") (pinfunction "~{INT}_17") (pintype "passive"))
    )
    (net (code "126") (name "unconnected-(U2-~{INT}-Pad17)") (class "Default")
      (node (ref "U2") (pin "17") (pinfunction "~{INT}_17") (pintype "passive"))
    )
    (net (code "127") (name "unconnected-(U3-OE-Pad8)") (class "Default")
      (node (ref "U3") (pin "8") (pinfunction "OE_8") (pintype "output"))
    )
  )
)
